# Buttons_wLED.net
KiCad netlist of a schematic drawn in Altium Designer
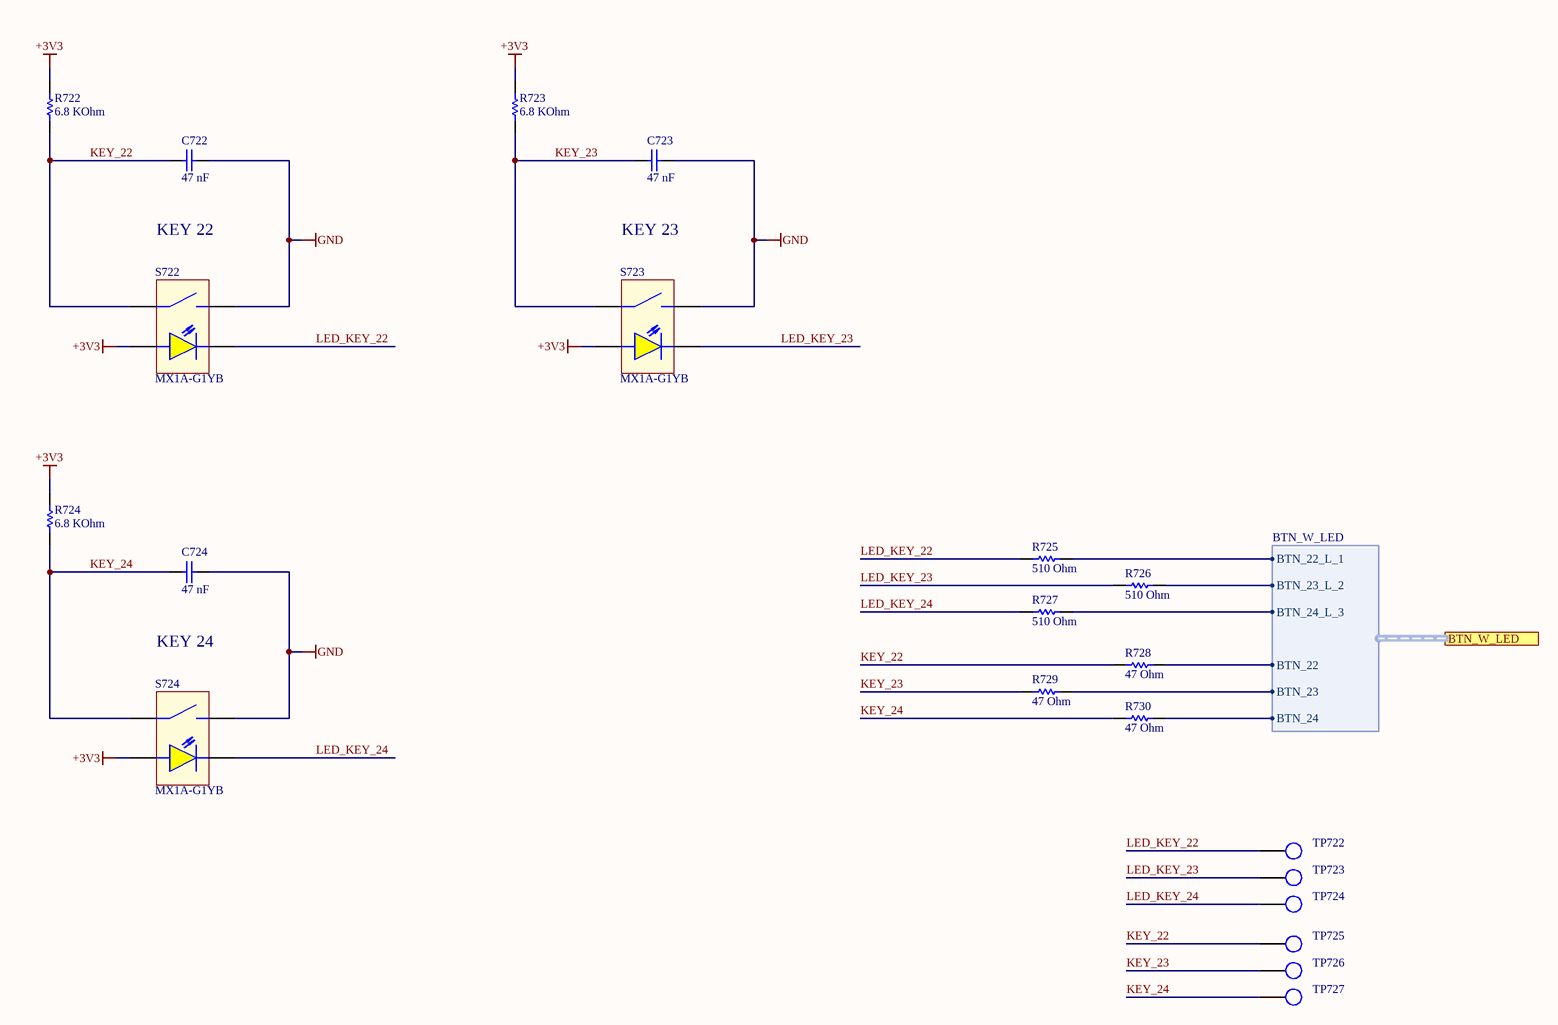
[diagram p0: Buttons wLED.SchDoc]

(export (version "E")
  (design (tool "Eeschema 10.0.6"))
  (components
    (comp (ref "C722")
      (value "CAP-47N")
      (footprint "CAPC0603")
      (description "Chip Capacitor, 47 nF, +/- 5%")
      (fields (field (name "TOLERANCE") "5 %") (field (name "CAPACITANCE") "47 nF"))
      (libsource (lib "Конденсаторы керамические SMD") (part "CAP-47N"))
    )
    (comp (ref "C723")
      (value "CAP-47N")
      (footprint "CAPC0603")
      (description "Chip Capacitor, 47 nF, +/- 5%")
      (fields (field (name "TOLERANCE") "5 %") (field (name "CAPACITANCE") "47 nF"))
      (libsource (lib "Конденсаторы керамические SMD") (part "CAP-47N"))
    )
    (comp (ref "C724")
      (value "CAP-47N")
      (footprint "CAPC0603")
      (description "Chip Capacitor, 47 nF, +/- 5%")
      (fields (field (name "TOLERANCE") "5 %") (field (name "CAPACITANCE") "47 nF"))
      (libsource (lib "Конденсаторы керамические SMD") (part "CAP-47N"))
    )
    (comp (ref "R722")
      (value "RES-6K8")
      (footprint "RES0603")
      (description "Chip Resistor, 6.8 KOhm, +/- 1%")
      (fields (field (name "TOLERANCE") "1 %") (field (name "RESISTANCE") "6.8 KOhm"))
      (libsource (lib "Резисторы SMD") (part "RES-6K8"))
    )
    (comp (ref "R723")
      (value "RES-6K8")
      (footprint "RES0603")
      (description "Chip Resistor, 6.8 KOhm, +/- 1%")
      (fields (field (name "TOLERANCE") "1 %") (field (name "RESISTANCE") "6.8 KOhm"))
      (libsource (lib "Резисторы SMD") (part "RES-6K8"))
    )
    (comp (ref "R724")
      (value "RES-6K8")
      (footprint "RES0603")
      (description "Chip Resistor, 6.8 KOhm, +/- 1%")
      (fields (field (name "TOLERANCE") "1 %") (field (name "RESISTANCE") "6.8 KOhm"))
      (libsource (lib "Резисторы SMD") (part "RES-6K8"))
    )
    (comp (ref "R725")
      (value "RES-510")
      (footprint "RES0603")
      (description "Chip Resistor, 510 Ohm, +/- 1%")
      (fields (field (name "TOLERANCE") "1 %") (field (name "RESISTANCE") "510 Ohm"))
      (libsource (lib "Резисторы SMD") (part "RES-510"))
    )
    (comp (ref "R726")
      (value "RES-510")
      (footprint "RES0603")
      (description "Chip Resistor, 510 Ohm, +/- 1%")
      (fields (field (name "TOLERANCE") "1 %") (field (name "RESISTANCE") "510 Ohm"))
      (libsource (lib "Резисторы SMD") (part "RES-510"))
    )
    (comp (ref "R727")
      (value "RES-510")
      (footprint "RES0603")
      (description "Chip Resistor, 510 Ohm, +/- 1%")
      (fields (field (name "TOLERANCE") "1 %") (field (name "RESISTANCE") "510 Ohm"))
      (libsource (lib "Резисторы SMD") (part "RES-510"))
    )
    (comp (ref "R728")
      (value "RES-47")
      (footprint "RES0603")
      (description "Chip Resistor, 47 Ohm, +/- 1%")
      (fields (field (name "TOLERANCE") "1 %") (field (name "RESISTANCE") "47 Ohm"))
      (libsource (lib "Резисторы SMD") (part "RES-47"))
    )
    (comp (ref "R729")
      (value "RES-47")
      (footprint "RES0603")
      (description "Chip Resistor, 47 Ohm, +/- 1%")
      (fields (field (name "TOLERANCE") "1 %") (field (name "RESISTANCE") "47 Ohm"))
      (libsource (lib "Резисторы SMD") (part "RES-47"))
    )
    (comp (ref "R730")
      (value "RES-47")
      (footprint "RES0603")
      (description "Chip Resistor, 47 Ohm, +/- 1%")
      (fields (field (name "TOLERANCE") "1 %") (field (name "RESISTANCE") "47 Ohm"))
      (libsource (lib "Резисторы SMD") (part "RES-47"))
    )
    (comp (ref "S722")
      (value "KEY 22")
      (footprint "CHERRY MX PCB WITH LED")
      (description "CHERRY MX Brown RGB Keyswitch 55cN Yellow LED")
      (fields (field (name "MODEL") "MX1A-G1YB"))
      (libsource (lib "Кнопки") (part "MX1A-G1YB"))
    )
    (comp (ref "S723")
      (value "KEY 23")
      (footprint "CHERRY MX PCB WITH LED")
      (description "CHERRY MX Brown RGB Keyswitch 55cN Yellow LED")
      (fields (field (name "MODEL") "MX1A-G1YB"))
      (libsource (lib "Кнопки") (part "MX1A-G1YB"))
    )
    (comp (ref "S724")
      (value "KEY 24")
      (footprint "CHERRY MX PCB WITH LED")
      (description "CHERRY MX Brown RGB Keyswitch 55cN Yellow LED")
      (fields (field (name "MODEL") "MX1A-G1YB"))
      (libsource (lib "Кнопки") (part "MX1A-G1YB"))
    )
    (comp (ref "TP722") (value "~") (footprint "TP_C-0.5mm") (libsource (lib "Разъемы") (part "TestPad")))
    (comp (ref "TP723") (value "~") (footprint "TP_C-0.5mm") (libsource (lib "Разъемы") (part "TestPad")))
    (comp (ref "TP724") (value "~") (footprint "TP_C-0.5mm") (libsource (lib "Разъемы") (part "TestPad")))
    (comp (ref "TP725") (value "~") (footprint "TP_C-0.5mm") (libsource (lib "Разъемы") (part "TestPad")))
    (comp (ref "TP726") (value "~") (footprint "TP_C-0.5mm") (libsource (lib "Разъемы") (part "TestPad")))
    (comp (ref "TP727") (value "~") (footprint "TP_C-0.5mm") (libsource (lib "Разъемы") (part "TestPad")))
  )
  (nets
    (net (code "2") (name "+3V3") (class "Default")
      (node (ref "R722") (pin "2") (pinfunction "2_2") (pintype "passive"))
      (node (ref "R723") (pin "2") (pinfunction "2_2") (pintype "passive"))
      (node (ref "R724") (pin "2") (pinfunction "2_2") (pintype "passive"))
      (node (ref "S722") (pin "A") (pintype "passive"))
      (node (ref "S723") (pin "A") (pintype "passive"))
      (node (ref "S724") (pin "A") (pintype "passive"))
    )
    (net (code "3") (name "/BTN_22") (class "Default")
      (node (ref "R728") (pin "2") (pinfunction "2_2") (pintype "passive"))
    )
    (net (code "4") (name "/BTN_22_L_1") (class "Default")
      (node (ref "R725") (pin "2") (pinfunction "2_2") (pintype "passive"))
    )
    (net (code "5") (name "/BTN_23") (class "Default")
      (node (ref "R729") (pin "2") (pinfunction "2_2") (pintype "passive"))
    )
    (net (code "6") (name "/BTN_23_L_2") (class "Default")
      (node (ref "R726") (pin "2") (pinfunction "2_2") (pintype "passive"))
    )
    (net (code "7") (name "/BTN_24") (class "Default")
      (node (ref "R730") (pin "2") (pinfunction "2_2") (pintype "passive"))
    )
    (net (code "8") (name "/BTN_24_L_3") (class "Default")
      (node (ref "R727") (pin "2") (pinfunction "2_2") (pintype "passive"))
    )
    (net (code "9") (name "/KEY_22") (class "Default")
      (node (ref "C722") (pin "1") (pinfunction "1_1") (pintype "passive"))
      (node (ref "R722") (pin "1") (pinfunction "1_1") (pintype "passive"))
      (node (ref "R728") (pin "1") (pinfunction "1_1") (pintype "passive"))
      (node (ref "S722") (pin "S1") (pintype "passive"))
      (node (ref "TP725") (pin "1") (pintype "passive"))
    )
    (net (code "10") (name "/KEY_23") (class "Default")
      (node (ref "C723") (pin "1") (pinfunction "1_1") (pintype "passive"))
      (node (ref "R723") (pin "1") (pinfunction "1_1") (pintype "passive"))
      (node (ref "R729") (pin "1") (pinfunction "1_1") (pintype "passive"))
      (node (ref "S723") (pin "S1") (pintype "passive"))
      (node (ref "TP726") (pin "1") (pintype "passive"))
    )
    (net (code "11") (name "/KEY_24") (class "Default")
      (node (ref "C724") (pin "1") (pinfunction "1_1") (pintype "passive"))
      (node (ref "R724") (pin "1") (pinfunction "1_1") (pintype "passive"))
      (node (ref "R730") (pin "1") (pinfunction "1_1") (pintype "passive"))
      (node (ref "S724") (pin "S1") (pintype "passive"))
      (node (ref "TP727") (pin "1") (pintype "passive"))
    )
    (net (code "12") (name "/LED_KEY_22") (class "Default")
      (node (ref "R725") (pin "1") (pinfunction "1_1") (pintype "passive"))
      (node (ref "S722") (pin "K") (pintype "passive"))
      (node (ref "TP722") (pin "1") (pintype "passive"))
    )
    (net (code "13") (name "/LED_KEY_23") (class "Default")
      (node (ref "R726") (pin "1") (pinfunction "1_1") (pintype "passive"))
      (node (ref "S723") (pin "K") (pintype "passive"))
      (node (ref "TP723") (pin "1") (pintype "passive"))
    )
    (net (code "14") (name "/LED_KEY_24") (class "Default")
      (node (ref "R727") (pin "1") (pinfunction "1_1") (pintype "passive"))
      (node (ref "S724") (pin "K") (pintype "passive"))
      (node (ref "TP724") (pin "1") (pintype "passive"))
    )
    (net (code "16") (name "GND") (class "Default")
      (node (ref "C722") (pin "2") (pinfunction "2_2") (pintype "passive"))
      (node (ref "C723") (pin "2") (pinfunction "2_2") (pintype "passive"))
      (node (ref "C724") (pin "2") (pinfunction "2_2") (pintype "passive"))
      (node (ref "S722") (pin "S2") (pintype "passive"))
      (node (ref "S723") (pin "S2") (pintype "passive"))
      (node (ref "S724") (pin "S2") (pintype "passive"))
    )
  )
)
